# AmbaSat-01-SHT3x-DIS.net
KiCad netlist of a schematic drawn in EAGLE
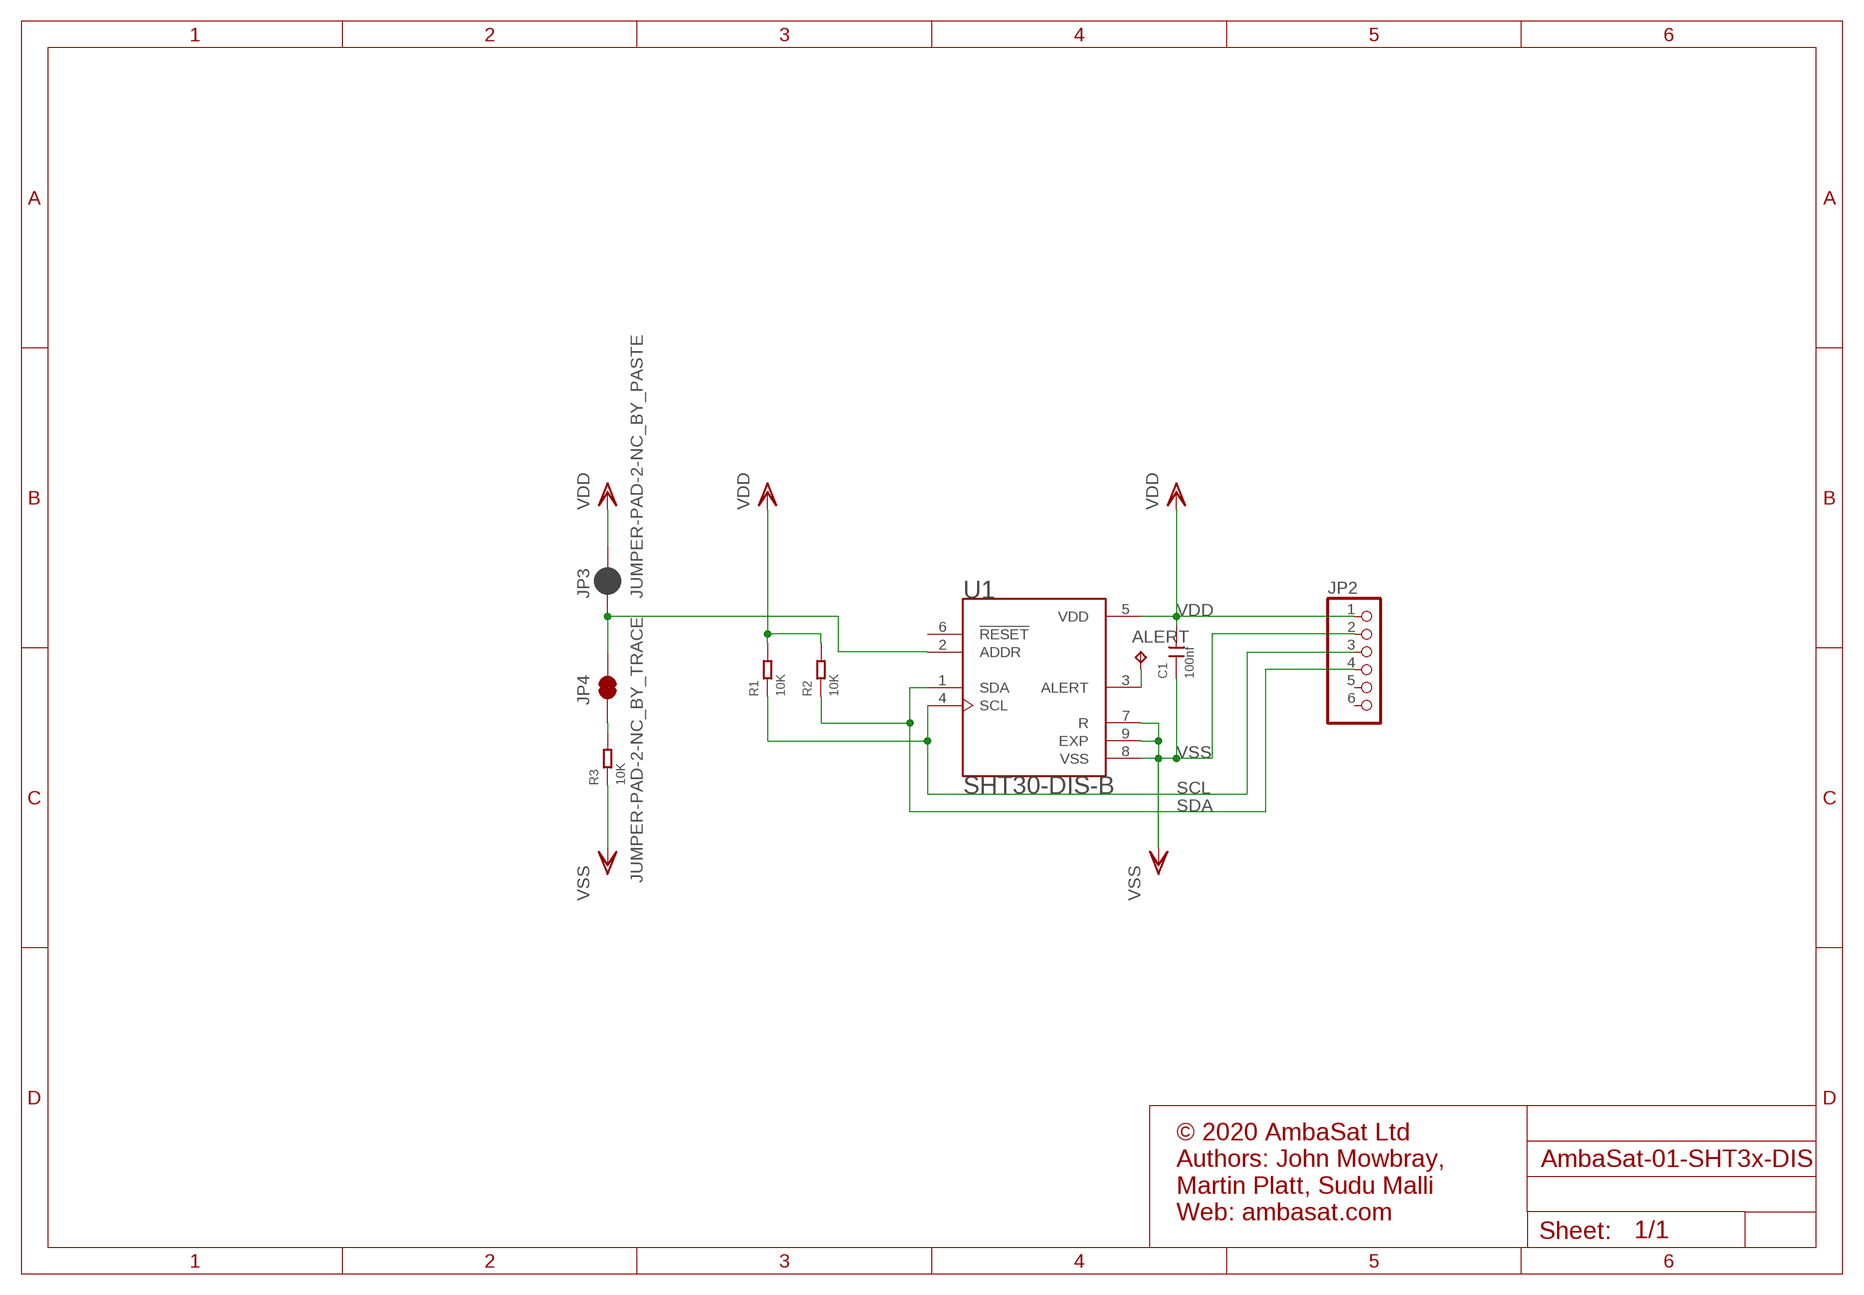
[diagram p0: schematic, sheet 1]

(export (version "E")
  (design (tool "Eeschema 10.0.6"))
  (components
    (comp (ref "ALERT")
      (value "TPTP06R")
      (footprint "eagle-import:TP06R")
      (libsource (lib "eagle-import") (part "TPTP06R"))
    )
    (comp (ref "C1")
      (value "100nf")
      (footprint "eagle-import:C0603")
      (fields (field (name "MPN") "CC0603KRX7R9BB104"))
      (libsource (lib "eagle-import") (part "CERAMIC-100NF-50V-10%-X7R(0603)"))
    )
    (comp (ref "JP2")
      (value "HEADER-1X6")
      (footprint "eagle-import:1X06_OVAL")
      (libsource (lib "eagle-import") (part "HEADER-1X6"))
    )
    (comp (ref "JP3")
      (value "JUMPER-PAD-2-NC_BY_PASTE")
      (footprint "eagle-import:PAD-JUMPER-2-NC_BY_PASTE_YES_SILK")
      (libsource (lib "eagle-import") (part "JUMPER-PAD-2-NC_BY_PASTE"))
    )
    (comp (ref "JP4")
      (value "JUMPER-PAD-2-NC_BY_TRACE")
      (footprint "eagle-import:PAD-JUMPER-2-NC_BY_TRACE_YES_SILK")
      (libsource (lib "eagle-import") (part "JUMPER-PAD-2-NC_BY_TRACE"))
    )
    (comp (ref "R1")
      (value "10K")
      (footprint "eagle-import:R0603")
      (fields (field (name "MPN") "RC0603FR-0710KL"))
      (libsource (lib "eagle-import") (part "SMD-RES-10K-1%-1/10W(0603)"))
    )
    (comp (ref "R2")
      (value "10K")
      (footprint "eagle-import:R0603")
      (fields (field (name "MPN") "RC0603FR-0710KL"))
      (libsource (lib "eagle-import") (part "SMD-RES-10K-1%-1/10W(0603)"))
    )
    (comp (ref "R3")
      (value "10K")
      (footprint "eagle-import:R0603")
      (fields (field (name "MPN") "RC0603FR-0710KL"))
      (libsource (lib "eagle-import") (part "SMD-RES-10K-1%-1/10W(0603)"))
    )
    (comp (ref "U1")
      (value "SHT30-DIS-B")
      (footprint "eagle-import:DFN250X250X100-9N")
      (fields (field (name "MF") "Sensirion AG"))
      (libsource (lib "eagle-import") (part "SHT30-DIS-B"))
    )
  )
  (nets
    (net (code "1") (name "/SCL") (class "Default")
      (node (ref "JP2") (pin "3") (pinfunction "3_3") (pintype "passive"))
      (node (ref "R1") (pin "1") (pinfunction "1_1") (pintype "passive"))
      (node (ref "U1") (pin "4") (pinfunction "SCL_4") (pintype "bidirectional"))
    )
    (net (code "2") (name "/SDA") (class "Default")
      (node (ref "JP2") (pin "4") (pinfunction "4_4") (pintype "passive"))
      (node (ref "R2") (pin "1") (pinfunction "1_1") (pintype "passive"))
      (node (ref "U1") (pin "1") (pinfunction "SDA_1") (pintype "bidirectional"))
    )
    (net (code "3") (name "Net-(JP4-Pad1)") (class "Default")
      (node (ref "JP4") (pin "1") (pinfunction "1_1") (pintype "passive"))
      (node (ref "R3") (pin "2") (pinfunction "2_2") (pintype "passive"))
    )
    (net (code "4") (name "Net-(U1-ADDR)") (class "Default")
      (node (ref "JP3") (pin "1") (pinfunction "1_1") (pintype "passive"))
      (node (ref "JP4") (pin "2") (pinfunction "2_2") (pintype "passive"))
      (node (ref "U1") (pin "2") (pinfunction "ADDR_2") (pintype "input"))
    )
    (net (code "5") (name "Net-(U1-ALERT)") (class "Default")
      (node (ref "ALERT") (pin "TP") (pinfunction "TP_TP") (pintype "input"))
      (node (ref "U1") (pin "3") (pinfunction "ALERT_3") (pintype "output"))
    )
    (net (code "6") (name "VDD") (class "Default")
      (node (ref "C1") (pin "2") (pinfunction "2_2") (pintype "passive"))
      (node (ref "JP2") (pin "1") (pinfunction "1_1") (pintype "passive"))
      (node (ref "JP3") (pin "2") (pinfunction "2_2") (pintype "passive"))
      (node (ref "R1") (pin "2") (pinfunction "2_2") (pintype "passive"))
      (node (ref "R2") (pin "2") (pinfunction "2_2") (pintype "passive"))
      (node (ref "U1") (pin "5") (pinfunction "VDD_5") (pintype "power_in"))
    )
    (net (code "7") (name "VSS") (class "Default")
      (node (ref "C1") (pin "1") (pinfunction "1_1") (pintype "passive"))
      (node (ref "JP2") (pin "2") (pinfunction "2_2") (pintype "passive"))
      (node (ref "R3") (pin "1") (pinfunction "1_1") (pintype "passive"))
      (node (ref "U1") (pin "7") (pinfunction "R_7") (pintype "passive"))
      (node (ref "U1") (pin "8") (pinfunction "VSS_8") (pintype "passive"))
      (node (ref "U1") (pin "9") (pinfunction "EXP_9") (pintype "passive"))
    )
    (net (code "8") (name "unconnected-(JP2-Pad5)") (class "Default")
      (node (ref "JP2") (pin "5") (pinfunction "5_5") (pintype "passive"))
    )
    (net (code "9") (name "unconnected-(JP2-Pad6)") (class "Default")
      (node (ref "JP2") (pin "6") (pinfunction "6_6") (pintype "passive"))
    )
    (net (code "10") (name "unconnected-(U1-~{RESET}-Pad6)") (class "Default")
      (node (ref "U1") (pin "6") (pinfunction "~{RESET}_6") (pintype "input"))
    )
  )
)
